# Video_out.net
KiCad netlist of a schematic drawn in Altium Designer
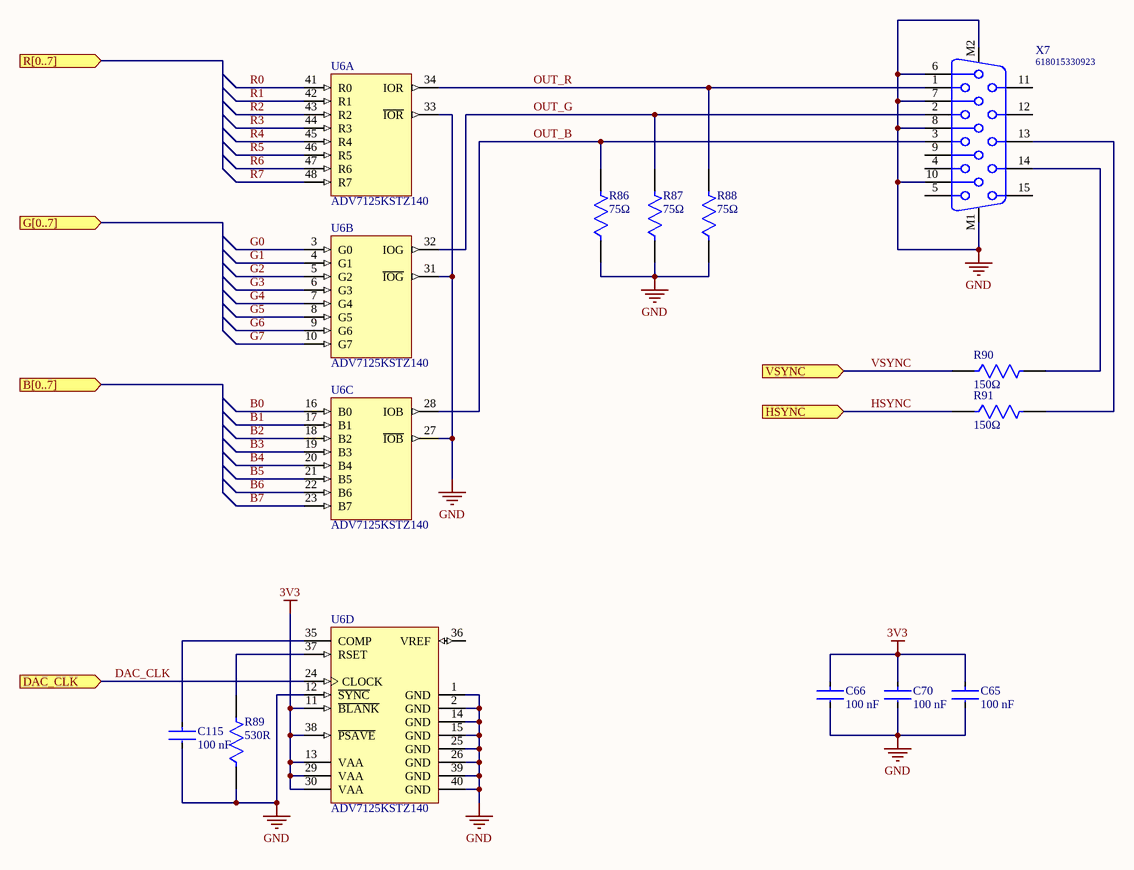
[diagram p0: Video out.SchDoc]

(export (version "E")
  (design (tool "Eeschema 10.0.6"))
  (components
    (comp (ref "C65")
      (value "CC0805KRX7R9BB104")
      (footprint "FP-CC0805-0_85-IPC_A")
      (description "CAP CER 0.1UF 50V X7R 0805")
      (fields (field (name "CAPACITANCE") "100 nF") (field (name "MANUFACTURER") "Yageo"))
      (libsource (lib "SchLib") (part "CMP-2100-03606-3"))
    )
    (comp (ref "C66")
      (value "CC0805KRX7R9BB104")
      (footprint "FP-CC0805-0_85-IPC_A")
      (description "CAP CER 0.1UF 50V X7R 0805")
      (fields (field (name "CAPACITANCE") "100 nF") (field (name "MANUFACTURER") "Yageo"))
      (libsource (lib "SchLib") (part "CMP-2100-03606-3"))
    )
    (comp (ref "C70")
      (value "CC0805KRX7R9BB104")
      (footprint "FP-CC0805-0_85-IPC_A")
      (description "CAP CER 0.1UF 50V X7R 0805")
      (fields (field (name "CAPACITANCE") "100 nF") (field (name "MANUFACTURER") "Yageo"))
      (libsource (lib "SchLib") (part "CMP-2100-03606-3"))
    )
    (comp (ref "C115")
      (value "CC0805KRX7R9BB104")
      (footprint "FP-CC0805-0_85-IPC_A")
      (description "CAP CER 0.1UF 50V X7R 0805")
      (fields (field (name "CAPACITANCE") "100 nF") (field (name "MANUFACTURER") "Yageo"))
      (libsource (lib "SchLib") (part "CMP-2100-03606-3"))
    )
    (comp (ref "R86")
      (value "RN73C2A75RBTDF")
      (footprint "FP-RN732A-IPC_A")
      (description "SMD Chip Resistor, Thin Film, 75Ω, 100 V, 0805 [2012 Metric], 100 mW, 0.1%, RN73 Series")
      (fields (field (name "MANUFACTURER") "TE Connectivity") (field (name "RESISTANCE") "75Ω"))
      (libsource (lib "SchLib") (part "CMP-03211-006560-1"))
    )
    (comp (ref "R87")
      (value "RN73C2A75RBTDF")
      (footprint "FP-RN732A-IPC_A")
      (description "SMD Chip Resistor, Thin Film, 75Ω, 100 V, 0805 [2012 Metric], 100 mW, 0.1%, RN73 Series")
      (fields (field (name "MANUFACTURER") "TE Connectivity") (field (name "RESISTANCE") "75Ω"))
      (libsource (lib "SchLib") (part "CMP-03211-006560-1"))
    )
    (comp (ref "R88")
      (value "RN73C2A75RBTDF")
      (footprint "FP-RN732A-IPC_A")
      (description "SMD Chip Resistor, Thin Film, 75Ω, 100 V, 0805 [2012 Metric], 100 mW, 0.1%, RN73 Series")
      (fields (field (name "MANUFACTURER") "TE Connectivity") (field (name "RESISTANCE") "75Ω"))
      (libsource (lib "SchLib") (part "CMP-03211-006560-1"))
    )
    (comp (ref "R89")
      (value "TNPW0805530RBETA")
      (footprint "FP-CRCW0805-HPe3-IPC_A")
      (description "RES Thick Film, 560Ω, 1%, 0.5W, 100ppm/°C, 0805")
      (fields
        (field (name "RESISTANCE") "530R")
        (field (name "MANUFACTURER") "Vishay")
        (field (name "MANUFACTURER PART NUMBER") "CRCW0805560RFKEAHP")
      )
      (libsource (lib "SchLib") (part "CMP-02407-005666-1"))
    )
    (comp (ref "R90")
      (value "RN73C2A150RBTDF")
      (footprint "FP-RN732A-IPC_A")
      (description "SMD Chip Resistor, Thin Film, 150Ω, 100 V, 0805 [2012 Metric], 100 mW, 0.1%, RN73 Series")
      (fields (field (name "RESISTANCE") "150Ω") (field (name "MANUFACTURER") "TE Connectivity"))
      (libsource (lib "SchLib") (part "CMP-03211-002331-1"))
    )
    (comp (ref "R91")
      (value "RN73C2A150RBTDF")
      (footprint "FP-RN732A-IPC_A")
      (description "SMD Chip Resistor, Thin Film, 150Ω, 100 V, 0805 [2012 Metric], 100 mW, 0.1%, RN73 Series")
      (fields (field (name "RESISTANCE") "150Ω") (field (name "MANUFACTURER") "TE Connectivity"))
      (libsource (lib "SchLib") (part "CMP-03211-002331-1"))
    )
    (comp (ref "U6")
      (value "ADV7125KSTZ140")
      (footprint "ST-48_N")
      (fields (field (name "MANUFACTURER") "Analog Devices"))
      (libsource (lib "SchLib") (part "CMP-0318-00718-2"))
    )
    (comp (ref "X7")
      (value "618015330923")
      (footprint "618015330923")
      (description "Female High Density PCB Connector with Hex Screw WR-DSUB, Angled, 15 pins")
      (fields (field (name "MANUFACTURER") "Wurth Electronics"))
      (libsource (lib "SchLib") (part "CMP-1502-00216-1"))
    )
  )
  (nets
    (net (code "1") (name "/B0") (class "Default")
      (node (ref "U6") (pin "16") (pinfunction "B0_16") (pintype "input"))
    )
    (net (code "2") (name "/B1") (class "Default")
      (node (ref "U6") (pin "17") (pinfunction "B1_17") (pintype "input"))
    )
    (net (code "3") (name "/B2") (class "Default")
      (node (ref "U6") (pin "18") (pinfunction "B2_18") (pintype "input"))
    )
    (net (code "4") (name "/B3") (class "Default")
      (node (ref "U6") (pin "19") (pinfunction "B3_19") (pintype "input"))
    )
    (net (code "5") (name "/B4") (class "Default")
      (node (ref "U6") (pin "20") (pinfunction "B4_20") (pintype "input"))
    )
    (net (code "6") (name "/B5") (class "Default")
      (node (ref "U6") (pin "21") (pinfunction "B5_21") (pintype "input"))
    )
    (net (code "7") (name "/B6") (class "Default")
      (node (ref "U6") (pin "22") (pinfunction "B6_22") (pintype "input"))
    )
    (net (code "8") (name "/B7") (class "Default")
      (node (ref "U6") (pin "23") (pinfunction "B7_23") (pintype "input"))
    )
    (net (code "10") (name "/DAC_CLK") (class "Default")
      (node (ref "U6") (pin "24") (pinfunction "CLOCK_24") (pintype "input"))
    )
    (net (code "11") (name "/G0") (class "Default")
      (node (ref "U6") (pin "3") (pinfunction "G0_3") (pintype "input"))
    )
    (net (code "12") (name "/G1") (class "Default")
      (node (ref "U6") (pin "4") (pinfunction "G1_4") (pintype "input"))
    )
    (net (code "13") (name "/G2") (class "Default")
      (node (ref "U6") (pin "5") (pinfunction "G2_5") (pintype "input"))
    )
    (net (code "14") (name "/G3") (class "Default")
      (node (ref "U6") (pin "6") (pinfunction "G3_6") (pintype "input"))
    )
    (net (code "15") (name "/G4") (class "Default")
      (node (ref "U6") (pin "7") (pinfunction "G4_7") (pintype "input"))
    )
    (net (code "16") (name "/G5") (class "Default")
      (node (ref "U6") (pin "8") (pinfunction "G5_8") (pintype "input"))
    )
    (net (code "17") (name "/G6") (class "Default")
      (node (ref "U6") (pin "9") (pinfunction "G6_9") (pintype "input"))
    )
    (net (code "18") (name "/G7") (class "Default")
      (node (ref "U6") (pin "10") (pinfunction "G7_10") (pintype "input"))
    )
    (net (code "20") (name "/HSYNC") (class "Default")
      (node (ref "R91") (pin "1") (pinfunction "1_1") (pintype "passive"))
    )
    (net (code "21") (name "/OUT_B") (class "Default")
      (node (ref "R86") (pin "2") (pinfunction "2_2") (pintype "passive"))
      (node (ref "U6") (pin "28") (pinfunction "IOB_28") (pintype "output"))
      (node (ref "X7") (pin "3") (pinfunction "3_3") (pintype "passive"))
    )
    (net (code "22") (name "/OUT_G") (class "Default")
      (node (ref "R87") (pin "2") (pinfunction "2_2") (pintype "passive"))
      (node (ref "U6") (pin "32") (pinfunction "IOG_32") (pintype "output"))
      (node (ref "X7") (pin "2") (pinfunction "2_2") (pintype "passive"))
    )
    (net (code "23") (name "/OUT_R") (class "Default")
      (node (ref "R88") (pin "2") (pinfunction "2_2") (pintype "passive"))
      (node (ref "U6") (pin "34") (pinfunction "IOR_34") (pintype "output"))
      (node (ref "X7") (pin "1") (pinfunction "1_1") (pintype "passive"))
    )
    (net (code "24") (name "/R0") (class "Default")
      (node (ref "U6") (pin "41") (pinfunction "R0_41") (pintype "input"))
    )
    (net (code "25") (name "/R1") (class "Default")
      (node (ref "U6") (pin "42") (pinfunction "R1_42") (pintype "input"))
    )
    (net (code "26") (name "/R2") (class "Default")
      (node (ref "U6") (pin "43") (pinfunction "R2_43") (pintype "input"))
    )
    (net (code "27") (name "/R3") (class "Default")
      (node (ref "U6") (pin "44") (pinfunction "R3_44") (pintype "input"))
    )
    (net (code "28") (name "/R4") (class "Default")
      (node (ref "U6") (pin "45") (pinfunction "R4_45") (pintype "input"))
    )
    (net (code "29") (name "/R5") (class "Default")
      (node (ref "U6") (pin "46") (pinfunction "R5_46") (pintype "input"))
    )
    (net (code "30") (name "/R6") (class "Default")
      (node (ref "U6") (pin "47") (pinfunction "R6_47") (pintype "input"))
    )
    (net (code "31") (name "/R7") (class "Default")
      (node (ref "U6") (pin "48") (pinfunction "R7_48") (pintype "input"))
    )
    (net (code "33") (name "/VSYNC") (class "Default")
      (node (ref "R90") (pin "1") (pinfunction "1_1") (pintype "passive"))
    )
    (net (code "34") (name "3V3") (class "Default")
      (node (ref "C65") (pin "1") (pinfunction "1_1") (pintype "passive"))
      (node (ref "C66") (pin "1") (pinfunction "1_1") (pintype "passive"))
      (node (ref "C70") (pin "1") (pinfunction "1_1") (pintype "passive"))
      (node (ref "U6") (pin "11") (pinfunction "~{BLANK}_11") (pintype "input"))
      (node (ref "U6") (pin "13") (pinfunction "VAA_13") (pintype "power_in"))
      (node (ref "U6") (pin "29") (pinfunction "VAA_29") (pintype "power_in"))
      (node (ref "U6") (pin "30") (pinfunction "VAA_30") (pintype "power_in"))
      (node (ref "U6") (pin "38") (pinfunction "~{PSAVE}_38") (pintype "input"))
    )
    (net (code "35") (name "GND") (class "Default")
      (node (ref "C115") (pin "2") (pinfunction "2_2") (pintype "passive"))
      (node (ref "C65") (pin "2") (pinfunction "2_2") (pintype "passive"))
      (node (ref "C66") (pin "2") (pinfunction "2_2") (pintype "passive"))
      (node (ref "C70") (pin "2") (pinfunction "2_2") (pintype "passive"))
      (node (ref "R86") (pin "1") (pinfunction "1_1") (pintype "passive"))
      (node (ref "R87") (pin "1") (pinfunction "1_1") (pintype "passive"))
      (node (ref "R88") (pin "1") (pinfunction "1_1") (pintype "passive"))
      (node (ref "R89") (pin "1") (pinfunction "1_1") (pintype "passive"))
      (node (ref "U6") (pin "1") (pinfunction "GND_1") (pintype "power_in"))
      (node (ref "U6") (pin "12") (pinfunction "~{SYNC}_12") (pintype "input"))
      (node (ref "U6") (pin "14") (pinfunction "GND_14") (pintype "power_in"))
      (node (ref "U6") (pin "15") (pinfunction "GND_15") (pintype "power_in"))
      (node (ref "U6") (pin "2") (pinfunction "GND_2") (pintype "power_in"))
      (node (ref "U6") (pin "25") (pinfunction "GND_25") (pintype "power_in"))
      (node (ref "U6") (pin "26") (pinfunction "GND_26") (pintype "power_in"))
      (node (ref "U6") (pin "27") (pinfunction "~{IOB}_27") (pintype "output"))
      (node (ref "U6") (pin "31") (pinfunction "~{IOG}_31") (pintype "output"))
      (node (ref "U6") (pin "33") (pinfunction "~{IOR}_33") (pintype "output"))
      (node (ref "U6") (pin "39") (pinfunction "GND_39") (pintype "power_in"))
      (node (ref "U6") (pin "40") (pinfunction "GND_40") (pintype "power_in"))
      (node (ref "X7") (pin "10") (pinfunction "10_10") (pintype "passive"))
      (node (ref "X7") (pin "6") (pinfunction "6_6") (pintype "passive"))
      (node (ref "X7") (pin "7") (pinfunction "7_7") (pintype "passive"))
      (node (ref "X7") (pin "8") (pinfunction "8_8") (pintype "passive"))
      (node (ref "X7") (pin "M1") (pinfunction "M1_M1") (pintype "passive"))
      (node (ref "X7") (pin "M2") (pinfunction "M2_M2") (pintype "passive"))
    )
    (net (code "36") (name "Net-(R90-Pad2)") (class "Default")
      (node (ref "R90") (pin "2") (pinfunction "2_2") (pintype "passive"))
      (node (ref "X7") (pin "14") (pinfunction "14_14") (pintype "passive"))
    )
    (net (code "37") (name "Net-(R91-Pad2)") (class "Default")
      (node (ref "R91") (pin "2") (pinfunction "2_2") (pintype "passive"))
      (node (ref "X7") (pin "13") (pinfunction "13_13") (pintype "passive"))
    )
    (net (code "38") (name "Net-(U6D-COMP)") (class "Default")
      (node (ref "C115") (pin "1") (pinfunction "1_1") (pintype "passive"))
      (node (ref "U6") (pin "35") (pinfunction "COMP_35") (pintype "passive"))
    )
    (net (code "39") (name "Net-(U6D-RSET)") (class "Default")
      (node (ref "R89") (pin "2") (pinfunction "2_2") (pintype "passive"))
      (node (ref "U6") (pin "37") (pinfunction "RSET_37") (pintype "input"))
    )
    (net (code "40") (name "unconnected-(U6D-VREF-Pad36)") (class "Default")
      (node (ref "U6") (pin "36") (pinfunction "VREF_36") (pintype "bidirectional"))
    )
    (net (code "41") (name "unconnected-(X7-Pad4)") (class "Default")
      (node (ref "X7") (pin "4") (pinfunction "4_4") (pintype "passive"))
    )
    (net (code "42") (name "unconnected-(X7-Pad5)") (class "Default")
      (node (ref "X7") (pin "5") (pinfunction "5_5") (pintype "passive"))
    )
    (net (code "43") (name "unconnected-(X7-Pad9)") (class "Default")
      (node (ref "X7") (pin "9") (pinfunction "9_9") (pintype "passive"))
    )
    (net (code "44") (name "unconnected-(X7-Pad11)") (class "Default")
      (node (ref "X7") (pin "11") (pinfunction "11_11") (pintype "passive"))
    )
    (net (code "45") (name "unconnected-(X7-Pad12)") (class "Default")
      (node (ref "X7") (pin "12") (pinfunction "12_12") (pintype "passive"))
    )
    (net (code "46") (name "unconnected-(X7-Pad15)") (class "Default")
      (node (ref "X7") (pin "15") (pinfunction "15_15") (pintype "passive"))
    )
  )
)
